# FanTempController.net
KiCad netlist of a schematic drawn in EasyEDA Pro
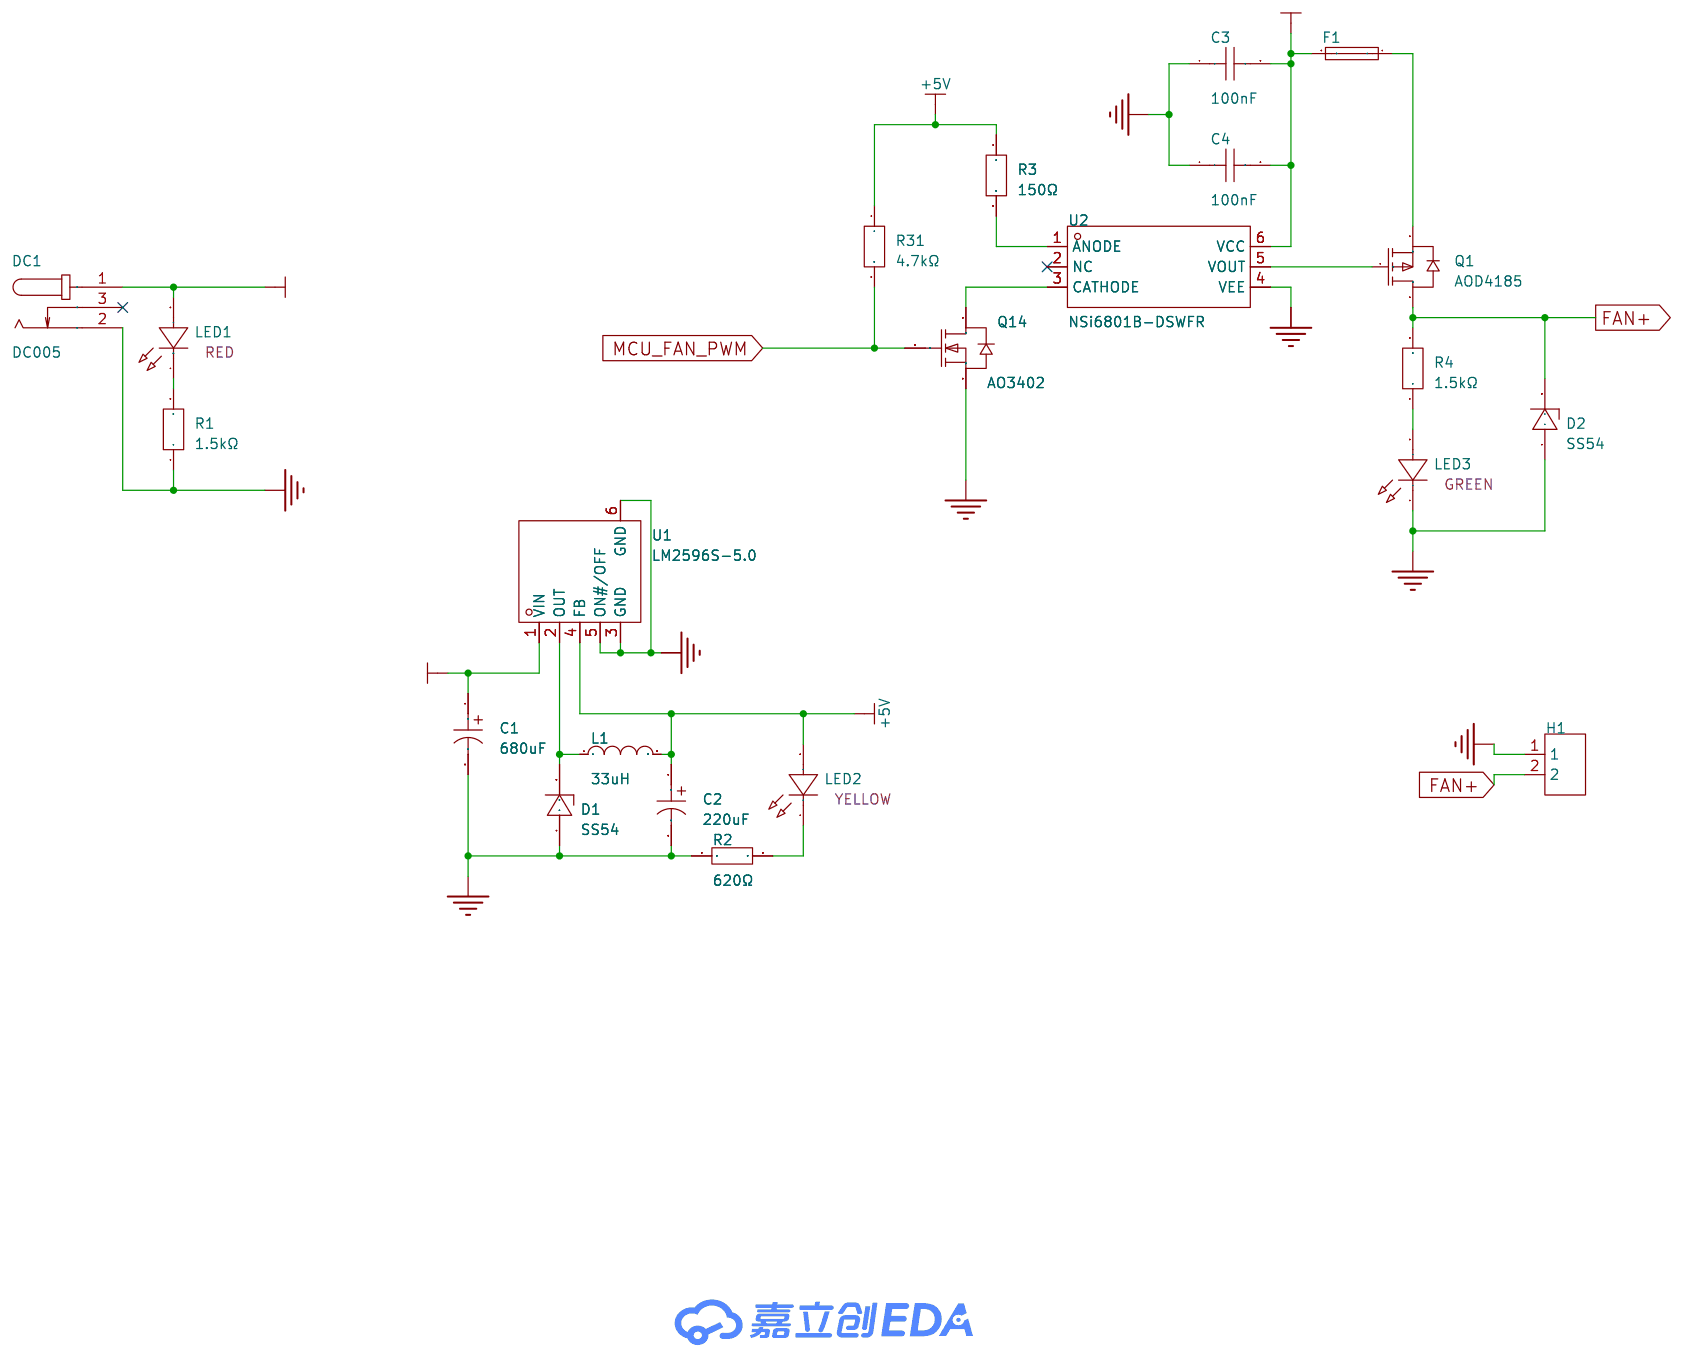
[diagram p0: Power]
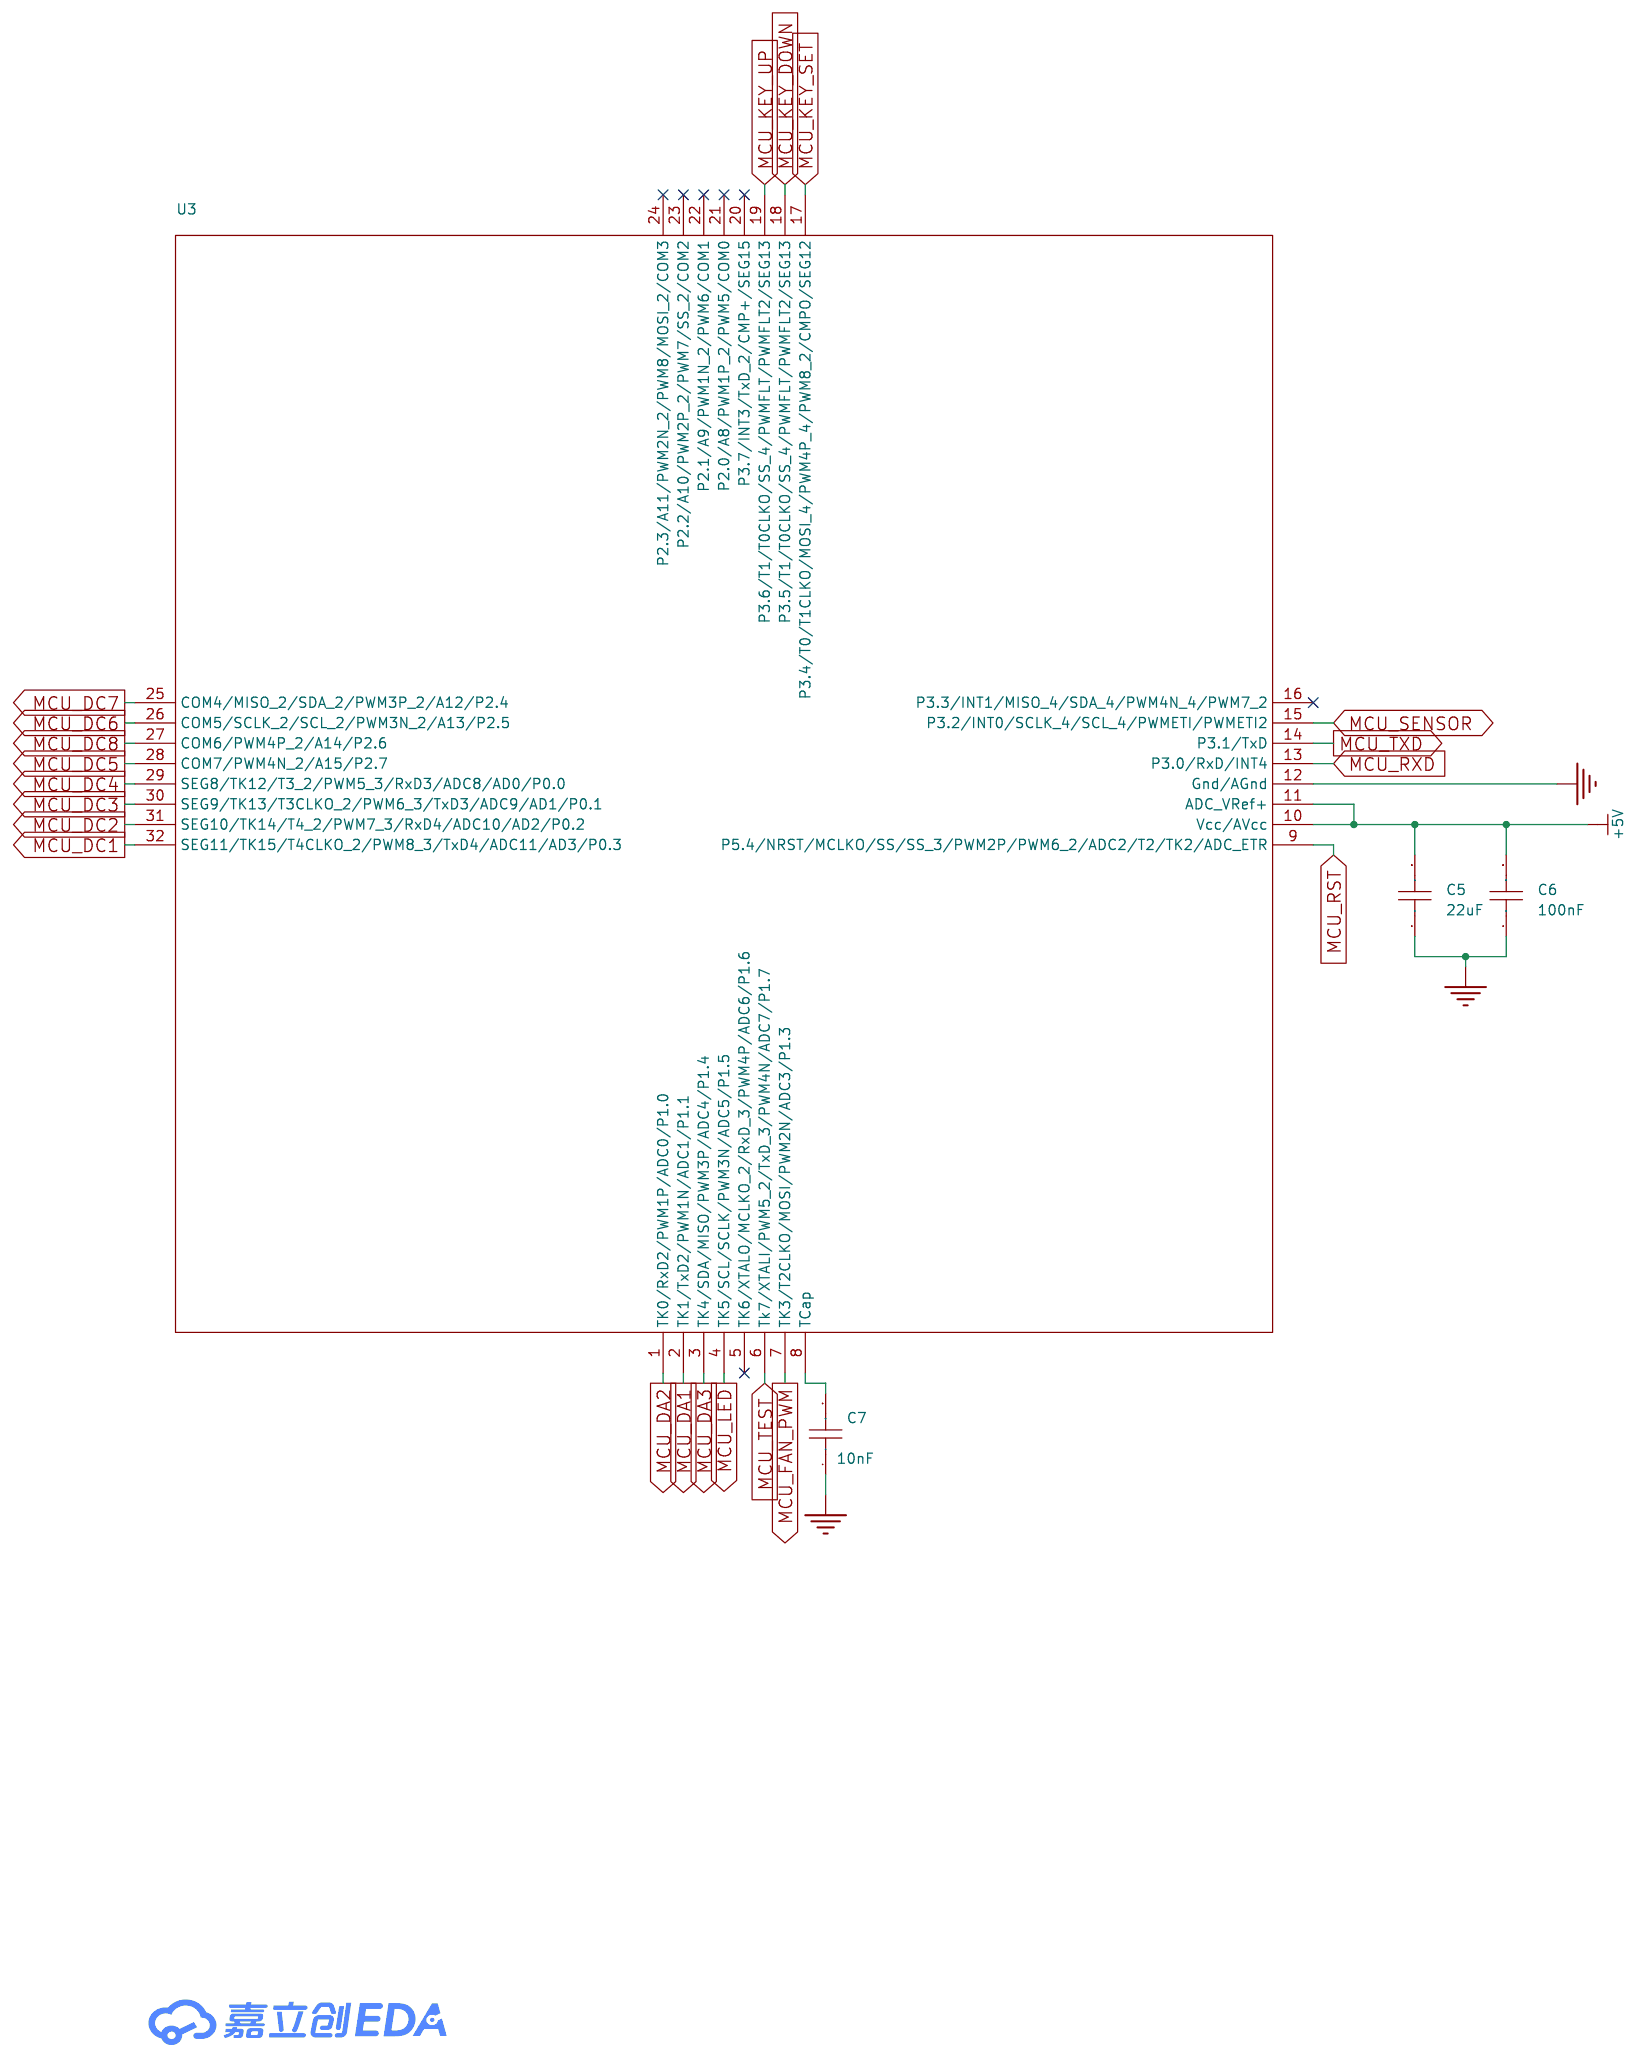
[diagram p1: MCU]
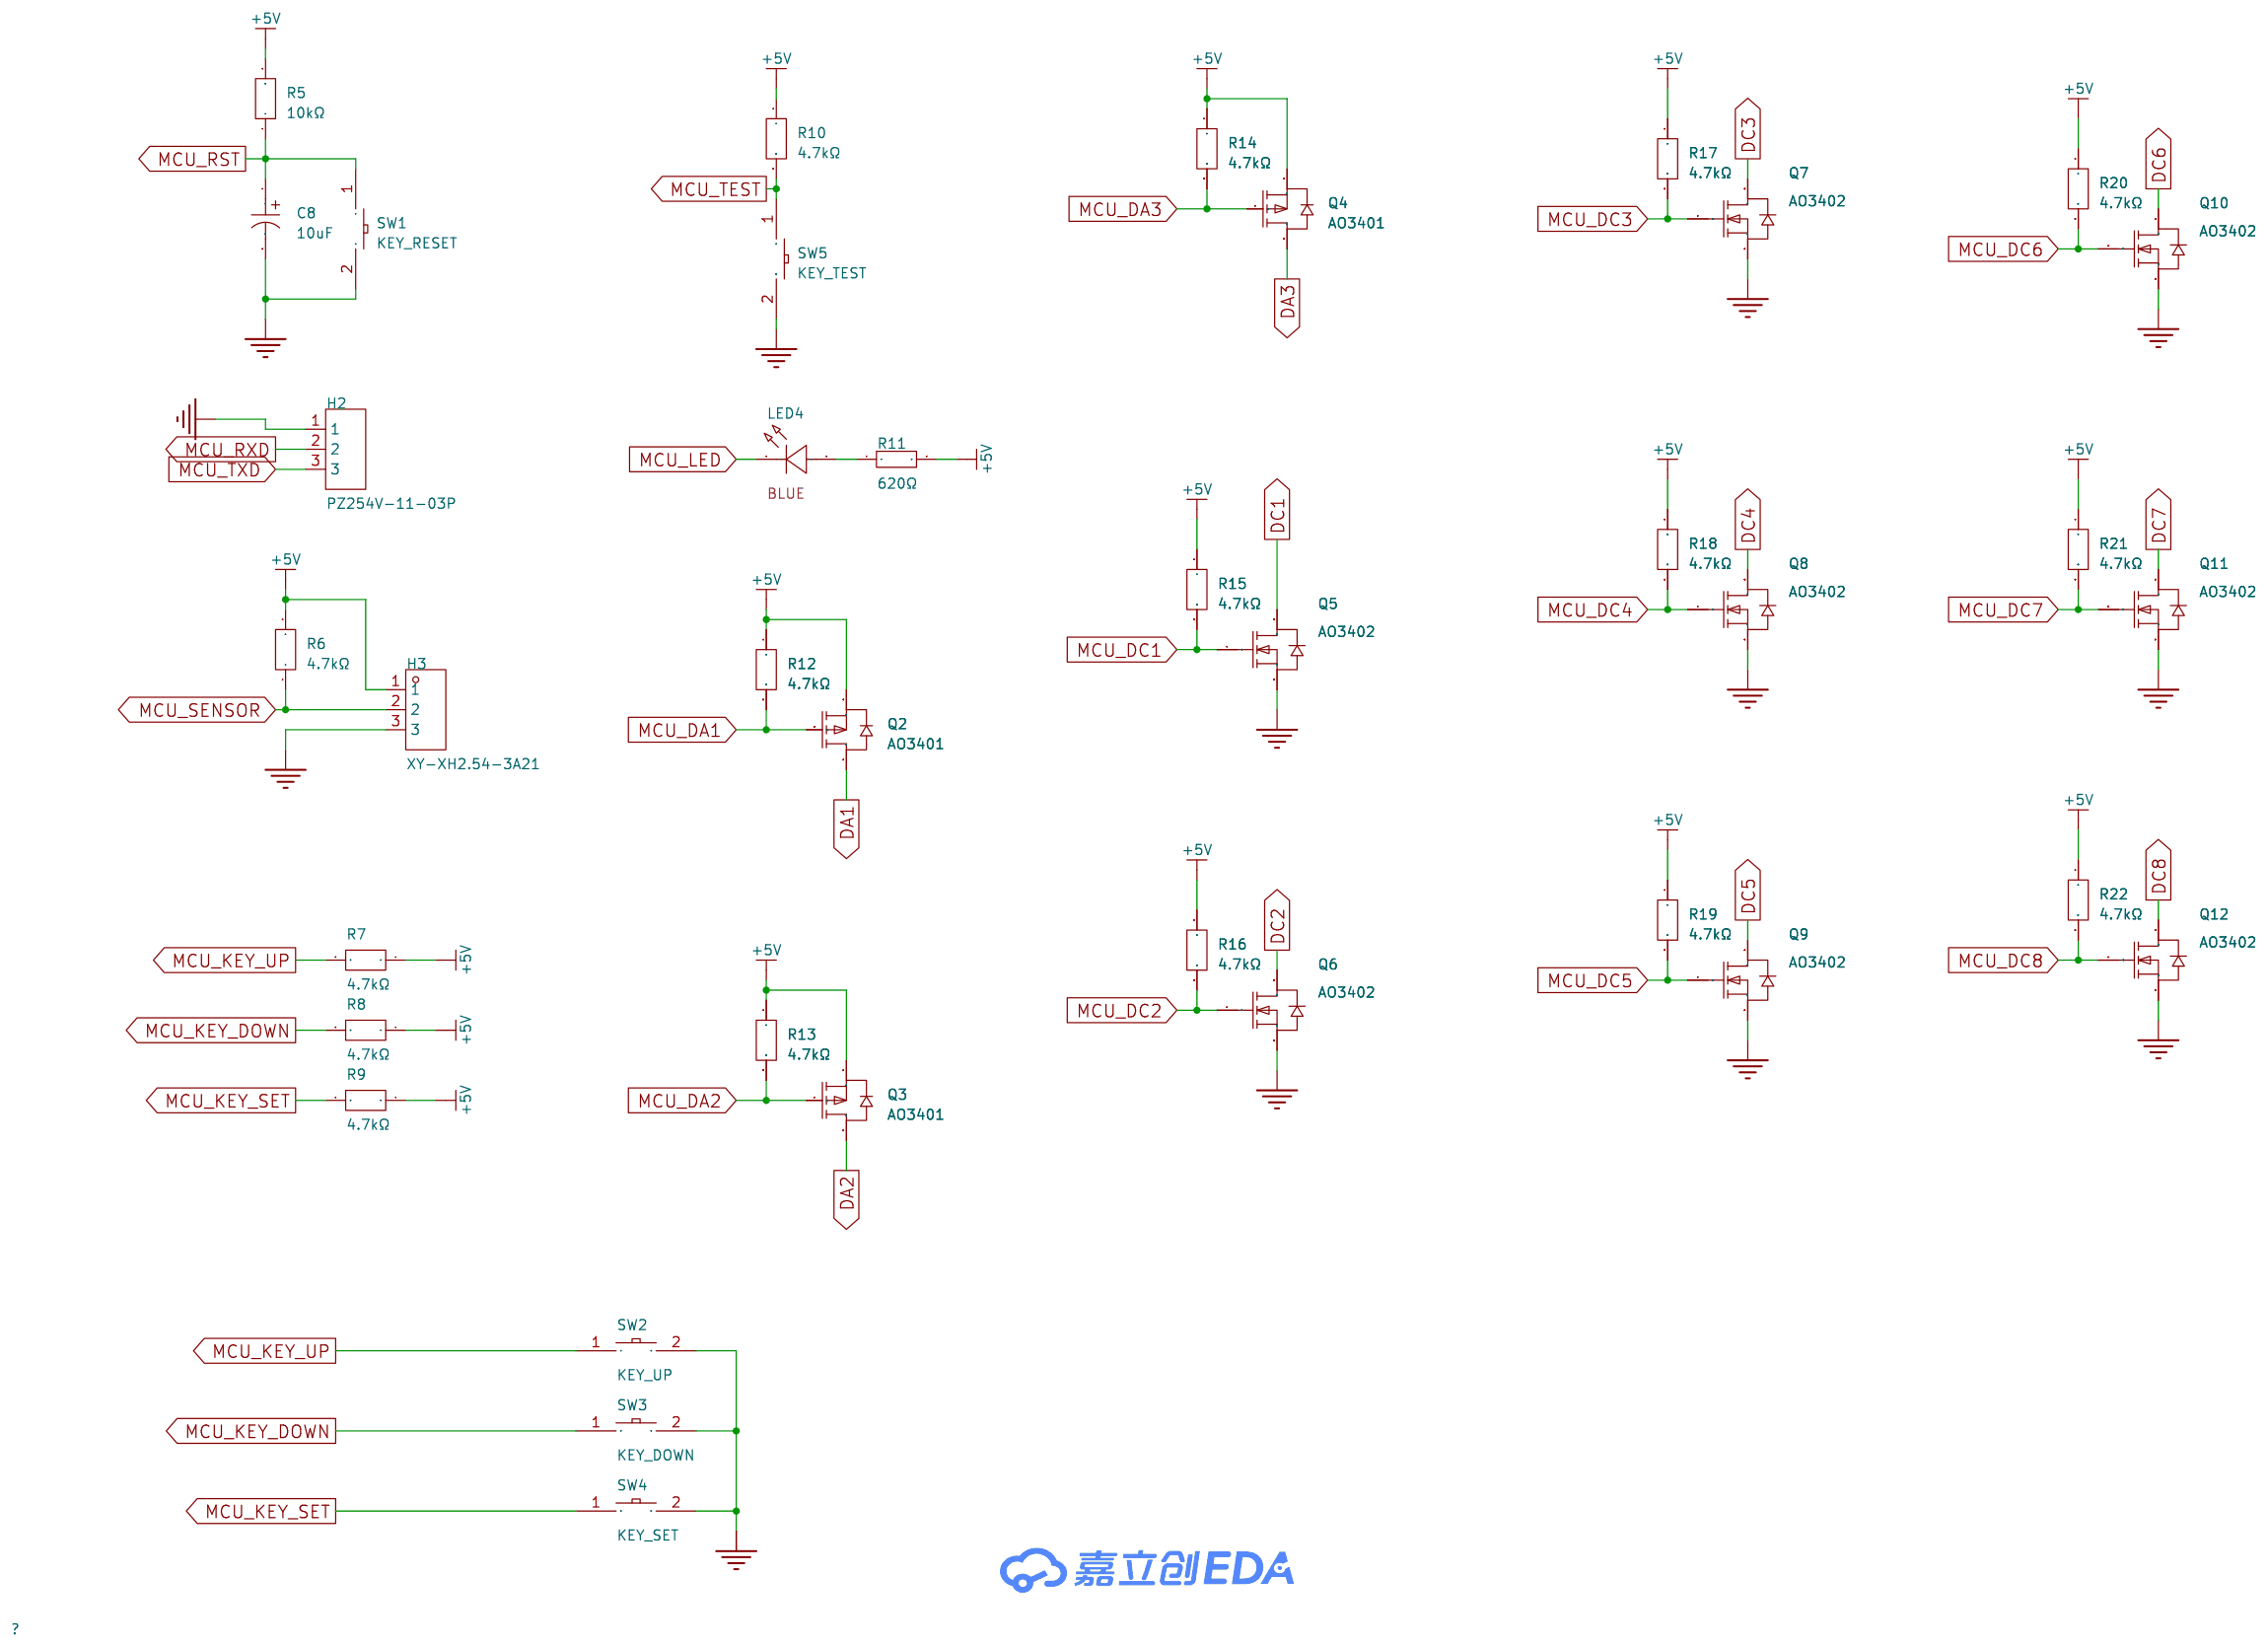
[diagram p2: Others]
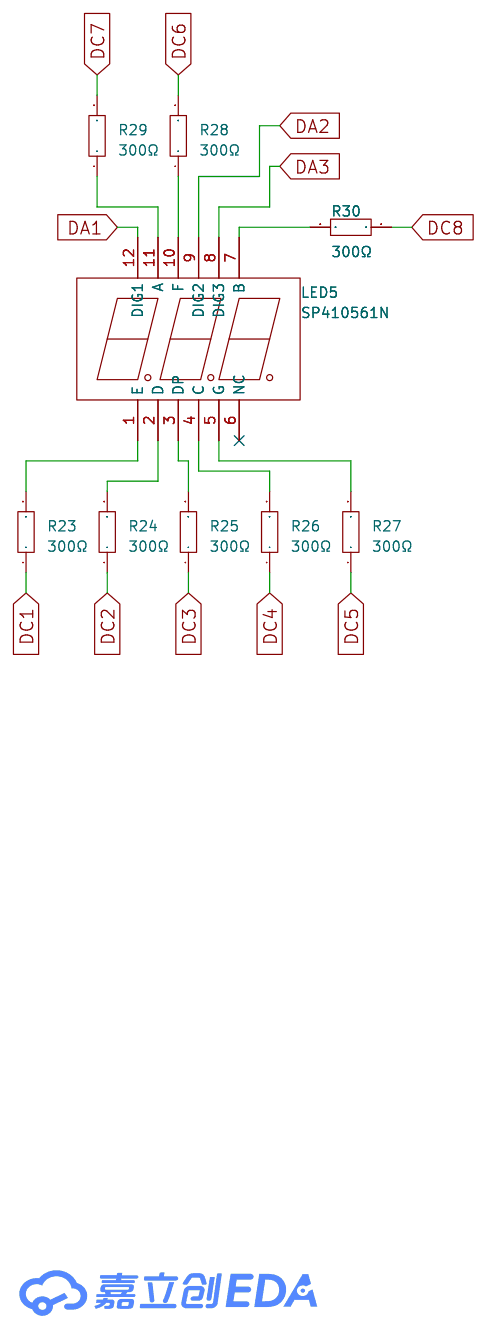
[diagram p3: Display]

(export (version "E")
  (design (tool "Eeschema 10.0.6"))
  (components
    (comp (ref "C1")
      (value "680uF")
      (footprint "easyedapro:CAP-SMD_BD10.0-L10.3-W10.3-LS11.0-FD")
      (description "容值:680uF;精度:±20%;额定电压:25V;纹波电流:670mA@100kHz;")
      (fields
        (field (name "Manufacturer Part") "GVE1E687M1010CN")
        (field (name "Manufacturer") "ACMECON(鼎容)")
      )
      (libsource (lib "easyedapro") (part "GVE1E687M1010CN"))
    )
    (comp (ref "C2")
      (value "220uF")
      (footprint "easyedapro:CAP-SMD_BD8.0-L8.3-W8.3-FD")
      (description "容值:220uF;精度:±20%;额定电压:35V;纹波电流:175mA@120Hz;")
      (fields
        (field (name "Manufacturer Part") "GVT1V227M0810CNVC")
        (field (name "Manufacturer") "HRK(鸿瑞凯电子)")
      )
      (libsource (lib "easyedapro") (part "GVT1V227M0810CNVC"))
    )
    (comp (ref "C3")
      (value "100nF")
      (footprint "easyedapro:C0805")
      (description "容值:100nF;精度:±10%;额定电压:50V;材质(温度系数):X7R;")
      (fields
        (field (name "Manufacturer Part") "C0805X104K5RAC7210")
        (field (name "Manufacturer") "KEMET(基美)")
      )
      (libsource (lib "easyedapro") (part "C0805X104K5RAC7210"))
    )
    (comp (ref "C4")
      (value "100nF")
      (footprint "easyedapro:C0805")
      (description "容值:100nF;精度:±10%;额定电压:50V;材质(温度系数):X7R;")
      (fields
        (field (name "Manufacturer Part") "C0805X104K5RAC7210")
        (field (name "Manufacturer") "KEMET(基美)")
      )
      (libsource (lib "easyedapro") (part "C0805X104K5RAC7210"))
    )
    (comp (ref "D1")
      (value "SS54")
      (footprint "easyedapro:SMA_L4.3-W2.6-LS5.0-FD")
      (description "二极管配置:独立式;正向压降(Vf):550mV@5.0A;直流反向耐压(Vr):40V;整流电流:5A;")
      (fields (field (name "Manufacturer") "宏迦橙"))
      (libsource (lib "easyedapro") (part "SS54_C7420369"))
    )
    (comp (ref "D2")
      (value "SS54")
      (footprint "easyedapro:SMA_L4.3-W2.6-LS5.0-FD")
      (description "二极管配置:独立式;正向压降(Vf):550mV@5.0A;直流反向耐压(Vr):40V;整流电流:5A;")
      (fields (field (name "Manufacturer") "宏迦橙"))
      (libsource (lib "easyedapro") (part "SS54_C7420369"))
    )
    (comp (ref "DC1")
      (value "DC005")
      (footprint "easyedapro:DC-IN-TH_DC005")
      (description "连接器类型:DC电源插座;安装方式:弯插;触点内径:2mm;触点外径:6.3mm;额定电流:500mA;额定电压:30V;工作温度范围:-25°C~+70°C;")
      (fields (field (name "Manufacturer") "SHOU HAN(首韩)"))
      (libsource (lib "easyedapro") (part "DC005_C431533"))
    )
    (comp (ref "F1")
      (value "SMD1812-200-30")
      (footprint "easyedapro:F1812")
      (description "耐压:30V;最大电流:40A;保持电流(Ih):2A;跳闸电流:4A;")
      (fields (field (name "Manufacturer") "宏嘉诚"))
      (libsource (lib "easyedapro") (part "SMD1812-200-30"))
    )
    (comp (ref "H1")
      (value "B25410120-2PB0513-H25A60")
      (footprint "easyedapro:HDR-TH_2P-P2.54-V-M-3")
      (fields (field (name "Manufacturer") "HMTCONN(华明通)"))
      (libsource (lib "easyedapro") (part "B25410120-2PB0513-H25A60"))
    )
    (comp (ref "L1")
      (value "33uH")
      (footprint "easyedapro:IND-SMD_L11.0-W10.2_CXP1050")
      (description "电感值:6.8uH;精度:±20%;额定电流:8.5A;饱和电流(Isat):13A;类型:一体成型电感;")
      (fields
        (field (name "Manufacturer Part") "CXP1050-6R8M-AG(6.8uh)")
        (field (name "Manufacturer") "DMBJ(振宝佳)")
      )
      (libsource (lib "easyedapro") (part "CXP1050-6R8M-AG(6.8UH)"))
    )
    (comp (ref "LED1")
      (value "LTL17KRH5D-012A")
      (footprint "easyedapro:LED-TH_BD3.8-P2.54-RD-RED")
      (description "发光颜色:红色;正向电流:-;")
      (fields (field (name "Manufacturer") "LITEON(光宝)") (field (name "Emitted Color") "RED"))
      (libsource (lib "easyedapro") (part "LTL17KRH5D-012A"))
    )
    (comp (ref "LED2")
      (value "LTL1KHKSD-071A")
      (footprint "easyedapro:LED-TH_BD3.8-P2.54-RD")
      (description "发光颜色:黄色;正向电流:-;")
      (fields (field (name "Manufacturer") "LITEON(光宝)") (field (name "Emitted Color") "YELLOW"))
      (libsource (lib "easyedapro") (part "LTL1KHKSD-071A"))
    )
    (comp (ref "LED3")
      (value "LTL1KHKSD-071A")
      (footprint "easyedapro:LED-TH_BD3.8-P2.54-RD")
      (description "发光颜色:黄色;正向电流:-;")
      (fields (field (name "Manufacturer") "LITEON(光宝)") (field (name "Emitted Color") "GREEN"))
      (libsource (lib "easyedapro") (part "LTL1KHKSD-071A"))
    )
    (comp (ref "Q1")
      (value "AOD4185")
      (footprint "easyedapro:TO-252-3_L6.6-W6.1-P4.57-LS9.9-BR-CW")
      (fields (field (name "Manufacturer") "AOS"))
      (libsource (lib "easyedapro") (part "AOD4185_C400894"))
    )
    (comp (ref "Q14")
      (value "AO3402")
      (footprint "easyedapro:SOT-23_L2.9-W1.3-P1.90-LS2.4-BR")
      (fields (field (name "Manufacturer") "AOS"))
      (libsource (lib "easyedapro") (part "AO3402_C14385"))
    )
    (comp (ref "R1")
      (value "1.5kΩ")
      (footprint "easyedapro:R0805")
      (description "电阻类型:厚膜电阻;阻值:1.5kΩ;精度:±1%;功率:125mW;工作电压:150V;温度系数:±100ppm/°C;")
      (fields (field (name "Manufacturer Part") "FRC0805F1501TS") (field (name "Manufacturer") "FOJAN(富捷)"))
      (libsource (lib "easyedapro") (part "FRC0805F1501TS"))
    )
    (comp (ref "R2")
      (value "620Ω")
      (footprint "easyedapro:R0805")
      (description "电阻类型:厚膜电阻;阻值:620Ω;精度:±1%;功率:125mW;最大工作电压:150V;温度系数:±100ppm/°C;")
      (fields
        (field (name "Manufacturer Part") "0805W8F6200T5E")
        (field (name "Manufacturer") "UNI-ROYAL(厚声)")
      )
      (libsource (lib "easyedapro") (part "0805W8F6200T5E"))
    )
    (comp (ref "R3")
      (value "150Ω")
      (footprint "easyedapro:R0805")
      (description "电阻类型:厚膜电阻;阻值:150Ω;精度:±5%;功率:125mW;最大工作电压:150V;温度系数:±100ppm/°C;")
      (fields (field (name "Manufacturer Part") "FRC0805J151 TS") (field (name "Manufacturer") "FOJAN(富捷)"))
      (libsource (lib "easyedapro") (part "FRC0805J151 TS"))
    )
    (comp (ref "R4")
      (value "1.5kΩ")
      (footprint "easyedapro:R0805")
      (description "电阻类型:厚膜电阻;阻值:1.5kΩ;精度:±1%;功率:125mW;工作电压:150V;温度系数:±100ppm/°C;")
      (fields (field (name "Manufacturer Part") "FRC0805F1501TS") (field (name "Manufacturer") "FOJAN(富捷)"))
      (libsource (lib "easyedapro") (part "FRC0805F1501TS"))
    )
    (comp (ref "R31")
      (value "4.7kΩ")
      (footprint "easyedapro:R0805")
      (description "电阻类型:厚膜电阻;阻值:4.7kΩ;精度:±1%;功率:250mW;工作电压:-;温度系数:±100ppm/°C;")
      (fields (field (name "Manufacturer Part") "SG73P2ATTD4701F") (field (name "Manufacturer") "KOA"))
      (libsource (lib "easyedapro") (part "SG73P2ATTD4701F"))
    )
    (comp (ref "U1")
      (value "LM2596S-5.0")
      (footprint "easyedapro:TO-263-5_L10.1-W8.7-P1.70-LS15.2-BR")
      (description "功能类型:降压型;输出类型:固定;工作电压:-;输出电压:5V;输出电流:-;")
      (fields (field (name "Manufacturer") "TWGMC(台湾迪嘉)"))
      (libsource (lib "easyedapro") (part "LM2596S-5.0_C5276750"))
    )
    (comp (ref "U2")
      (value "NSi6801B-DSWFR")
      (footprint "easyedapro:SOIC-6_L7.5-W4.7-P1.27-LS11.50-TL")
      (fields (field (name "Manufacturer") "NOVOSENSE(纳芯微)"))
      (libsource (lib "easyedapro") (part "NSI6801B-DSWFR"))
    )
    (comp (ref "C5")
      (value "22uF")
      (footprint "easyedapro:C0805")
      (description "容值:22uF;精度:±20%;额定电压:6.3V;温度系数:X7T;")
      (fields
        (field (name "Manufacturer Part") "CL21Z226MQYVPNE")
        (field (name "Manufacturer") "SAMSUNG(三星)")
      )
      (libsource (lib "easyedapro") (part "CL21Z226MQYVPNE"))
    )
    (comp (ref "C6")
      (value "100nF")
      (footprint "easyedapro:C0805")
      (description "容值:100nF;精度:±10%;额定电压:50V;材质(温度系数):X7R;")
      (fields
        (field (name "Manufacturer Part") "C0805X104K5RAC7210")
        (field (name "Manufacturer") "KEMET(基美)")
      )
      (libsource (lib "easyedapro") (part "C0805X104K5RAC7210"))
    )
    (comp (ref "C7")
      (value "10nF")
      (footprint "easyedapro:C0805")
      (description "容值:10nF;精度:±2%;额定电压:50V;材质(温度系数):X8G;")
      (fields
        (field (name "Manufacturer Part") "GCM21B5G1H103GA16L")
        (field (name "Manufacturer") "muRata(村田)")
      )
      (libsource (lib "easyedapro") (part "GCM21B5G1H103GA16L"))
    )
    (comp (ref "U3")
      (value "~")
      (footprint "easyedapro:LQFP-32_L7.0-W7.0-P0.80-LS9.0-BL")
      (description "STC8H4K64TL-40I-LQFP32")
      (libsource (lib "easyedapro") (part "STC8H4K64TL-40I-LQFP32"))
    )
    (comp (ref "C8")
      (value "10uF")
      (footprint "easyedapro:CAP-SMD_BD4.0-L4.3-W4.3-LS5.0-FD")
      (description "容值:10uF;精度:±20%;额定电压:16V;纹波电流:17mA@120Hz;")
      (fields (field (name "Manufacturer Part") "RVT16V10M4X5") (field (name "Manufacturer") "捷而瑞"))
      (libsource (lib "easyedapro") (part "RVT16V10M4X5"))
    )
    (comp (ref "H2")
      (value "PZ254V-11-03P")
      (footprint "easyedapro:HDR-TH_3P-P2.54-V-M")
      (fields (field (name "Manufacturer") "XFCN(兴飞)"))
      (libsource (lib "easyedapro") (part "PZ254V-11-03P_C2937625"))
    )
    (comp (ref "H3")
      (value "XY-XH2.54-3A21")
      (footprint "easyedapro:HDR-TH_3P-P2.50-H-F-W7.0-N")
      (description "插针结构:1x3P;间距:2.54mm;安装方式:弯插;总PIN数:3P;排数:1;每排PIN数:3;行距:2.54mm;额定电流:3A;工作温度范围:-25°C~+85°C;")
      (fields (field (name "Manufacturer") "XYECONN(辛译)"))
      (libsource (lib "easyedapro") (part "XY-XH2.54-3A21"))
    )
    (comp (ref "LED4")
      (value "LTL1KHKSD-071A")
      (footprint "easyedapro:LED-TH_BD3.8-P2.54-RD")
      (description "发光颜色:黄色;正向电流:-;")
      (fields (field (name "Manufacturer") "LITEON(光宝)") (field (name "Emitted Color") "BLUE"))
      (libsource (lib "easyedapro") (part "LTL1KHKSD-071A"))
    )
    (comp (ref "Q2")
      (value "AO3401")
      (footprint "easyedapro:SOT-23-3_L2.9-W1.6-P1.90-LS2.8-BR")
      (description "漏源耐压：-30V 漏极电流：-4.4A 大体积 P MOS")
      (fields (field (name "Manufacturer") "FOSAN(富捷/富信)"))
      (libsource (lib "easyedapro") (part "AO3401_C20634975"))
    )
    (comp (ref "Q3")
      (value "AO3401")
      (footprint "easyedapro:SOT-23-3_L2.9-W1.6-P1.90-LS2.8-BR")
      (description "漏源耐压：-30V 漏极电流：-4.4A 大体积 P MOS")
      (fields (field (name "Manufacturer") "FOSAN(富捷/富信)"))
      (libsource (lib "easyedapro") (part "AO3401_C20634975"))
    )
    (comp (ref "Q4")
      (value "AO3401")
      (footprint "easyedapro:SOT-23-3_L2.9-W1.6-P1.90-LS2.8-BR")
      (description "漏源耐压：-30V 漏极电流：-4.4A 大体积 P MOS")
      (fields (field (name "Manufacturer") "FOSAN(富捷/富信)"))
      (libsource (lib "easyedapro") (part "AO3401_C20634975"))
    )
    (comp (ref "Q5")
      (value "AO3402")
      (footprint "easyedapro:SOT-23_L2.9-W1.3-P1.90-LS2.4-BR")
      (fields (field (name "Manufacturer") "AOS"))
      (libsource (lib "easyedapro") (part "AO3402_C14385"))
    )
    (comp (ref "Q6")
      (value "AO3402")
      (footprint "easyedapro:SOT-23_L2.9-W1.3-P1.90-LS2.4-BR")
      (fields (field (name "Manufacturer") "AOS"))
      (libsource (lib "easyedapro") (part "AO3402_C14385"))
    )
    (comp (ref "Q7")
      (value "AO3402")
      (footprint "easyedapro:SOT-23_L2.9-W1.3-P1.90-LS2.4-BR")
      (fields (field (name "Manufacturer") "AOS"))
      (libsource (lib "easyedapro") (part "AO3402_C14385"))
    )
    (comp (ref "Q8")
      (value "AO3402")
      (footprint "easyedapro:SOT-23_L2.9-W1.3-P1.90-LS2.4-BR")
      (fields (field (name "Manufacturer") "AOS"))
      (libsource (lib "easyedapro") (part "AO3402_C14385"))
    )
    (comp (ref "Q9")
      (value "AO3402")
      (footprint "easyedapro:SOT-23_L2.9-W1.3-P1.90-LS2.4-BR")
      (fields (field (name "Manufacturer") "AOS"))
      (libsource (lib "easyedapro") (part "AO3402_C14385"))
    )
    (comp (ref "Q10")
      (value "AO3402")
      (footprint "easyedapro:SOT-23_L2.9-W1.3-P1.90-LS2.4-BR")
      (fields (field (name "Manufacturer") "AOS"))
      (libsource (lib "easyedapro") (part "AO3402_C14385"))
    )
    (comp (ref "Q11")
      (value "AO3402")
      (footprint "easyedapro:SOT-23_L2.9-W1.3-P1.90-LS2.4-BR")
      (fields (field (name "Manufacturer") "AOS"))
      (libsource (lib "easyedapro") (part "AO3402_C14385"))
    )
    (comp (ref "Q12")
      (value "AO3402")
      (footprint "easyedapro:SOT-23_L2.9-W1.3-P1.90-LS2.4-BR")
      (fields (field (name "Manufacturer") "AOS"))
      (libsource (lib "easyedapro") (part "AO3402_C14385"))
    )
    (comp (ref "R5")
      (value "10kΩ")
      (footprint "easyedapro:R0805")
      (description "阻值:10kΩ;精度:±1%;功率:125mW;")
      (fields (field (name "Manufacturer Part") "RCA0510KFLF") (field (name "Manufacturer") "HKR(香港电阻)"))
      (libsource (lib "easyedapro") (part "RCA0510KFLF"))
    )
    (comp (ref "R6")
      (value "4.7kΩ")
      (footprint "easyedapro:R0805")
      (description "电阻类型:厚膜电阻;阻值:4.7kΩ;精度:±1%;功率:250mW;工作电压:-;温度系数:±100ppm/°C;")
      (fields (field (name "Manufacturer Part") "SG73P2ATTD4701F") (field (name "Manufacturer") "KOA"))
      (libsource (lib "easyedapro") (part "SG73P2ATTD4701F"))
    )
    (comp (ref "R7")
      (value "4.7kΩ")
      (footprint "easyedapro:R0805")
      (description "电阻类型:厚膜电阻;阻值:4.7kΩ;精度:±1%;功率:250mW;工作电压:-;温度系数:±100ppm/°C;")
      (fields (field (name "Manufacturer Part") "SG73P2ATTD4701F") (field (name "Manufacturer") "KOA"))
      (libsource (lib "easyedapro") (part "SG73P2ATTD4701F"))
    )
    (comp (ref "R8")
      (value "4.7kΩ")
      (footprint "easyedapro:R0805")
      (description "电阻类型:厚膜电阻;阻值:4.7kΩ;精度:±1%;功率:250mW;工作电压:-;温度系数:±100ppm/°C;")
      (fields (field (name "Manufacturer Part") "SG73P2ATTD4701F") (field (name "Manufacturer") "KOA"))
      (libsource (lib "easyedapro") (part "SG73P2ATTD4701F"))
    )
    (comp (ref "R9")
      (value "4.7kΩ")
      (footprint "easyedapro:R0805")
      (description "电阻类型:厚膜电阻;阻值:4.7kΩ;精度:±1%;功率:250mW;工作电压:-;温度系数:±100ppm/°C;")
      (fields (field (name "Manufacturer Part") "SG73P2ATTD4701F") (field (name "Manufacturer") "KOA"))
      (libsource (lib "easyedapro") (part "SG73P2ATTD4701F"))
    )
    (comp (ref "R10")
      (value "4.7kΩ")
      (footprint "easyedapro:R0805")
      (description "电阻类型:厚膜电阻;阻值:4.7kΩ;精度:±1%;功率:250mW;工作电压:-;温度系数:±100ppm/°C;")
      (fields (field (name "Manufacturer Part") "SG73P2ATTD4701F") (field (name "Manufacturer") "KOA"))
      (libsource (lib "easyedapro") (part "SG73P2ATTD4701F"))
    )
    (comp (ref "R11")
      (value "620Ω")
      (footprint "easyedapro:R0805")
      (description "电阻类型:厚膜电阻;阻值:620Ω;精度:±1%;功率:125mW;最大工作电压:150V;温度系数:±100ppm/°C;")
      (fields
        (field (name "Manufacturer Part") "0805W8F6200T5E")
        (field (name "Manufacturer") "UNI-ROYAL(厚声)")
      )
      (libsource (lib "easyedapro") (part "0805W8F6200T5E"))
    )
    (comp (ref "R12")
      (value "4.7kΩ")
      (footprint "easyedapro:R0805")
      (description "电阻类型:厚膜电阻;阻值:4.7kΩ;精度:±1%;功率:250mW;工作电压:-;温度系数:±100ppm/°C;")
      (fields (field (name "Manufacturer Part") "SG73P2ATTD4701F") (field (name "Manufacturer") "KOA"))
      (libsource (lib "easyedapro") (part "SG73P2ATTD4701F"))
    )
    (comp (ref "R13")
      (value "4.7kΩ")
      (footprint "easyedapro:R0805")
      (description "电阻类型:厚膜电阻;阻值:4.7kΩ;精度:±1%;功率:250mW;工作电压:-;温度系数:±100ppm/°C;")
      (fields (field (name "Manufacturer Part") "SG73P2ATTD4701F") (field (name "Manufacturer") "KOA"))
      (libsource (lib "easyedapro") (part "SG73P2ATTD4701F"))
    )
    (comp (ref "R14")
      (value "4.7kΩ")
      (footprint "easyedapro:R0805")
      (description "电阻类型:厚膜电阻;阻值:4.7kΩ;精度:±1%;功率:250mW;工作电压:-;温度系数:±100ppm/°C;")
      (fields (field (name "Manufacturer Part") "SG73P2ATTD4701F") (field (name "Manufacturer") "KOA"))
      (libsource (lib "easyedapro") (part "SG73P2ATTD4701F"))
    )
    (comp (ref "R15")
      (value "4.7kΩ")
      (footprint "easyedapro:R0805")
      (description "电阻类型:厚膜电阻;阻值:4.7kΩ;精度:±1%;功率:250mW;工作电压:-;温度系数:±100ppm/°C;")
      (fields (field (name "Manufacturer Part") "SG73P2ATTD4701F") (field (name "Manufacturer") "KOA"))
      (libsource (lib "easyedapro") (part "SG73P2ATTD4701F"))
    )
    (comp (ref "R16")
      (value "4.7kΩ")
      (footprint "easyedapro:R0805")
      (description "电阻类型:厚膜电阻;阻值:4.7kΩ;精度:±1%;功率:250mW;工作电压:-;温度系数:±100ppm/°C;")
      (fields (field (name "Manufacturer Part") "SG73P2ATTD4701F") (field (name "Manufacturer") "KOA"))
      (libsource (lib "easyedapro") (part "SG73P2ATTD4701F"))
    )
    (comp (ref "R17")
      (value "4.7kΩ")
      (footprint "easyedapro:R0805")
      (description "电阻类型:厚膜电阻;阻值:4.7kΩ;精度:±1%;功率:250mW;工作电压:-;温度系数:±100ppm/°C;")
      (fields (field (name "Manufacturer Part") "SG73P2ATTD4701F") (field (name "Manufacturer") "KOA"))
      (libsource (lib "easyedapro") (part "SG73P2ATTD4701F"))
    )
    (comp (ref "R18")
      (value "4.7kΩ")
      (footprint "easyedapro:R0805")
      (description "电阻类型:厚膜电阻;阻值:4.7kΩ;精度:±1%;功率:250mW;工作电压:-;温度系数:±100ppm/°C;")
      (fields (field (name "Manufacturer Part") "SG73P2ATTD4701F") (field (name "Manufacturer") "KOA"))
      (libsource (lib "easyedapro") (part "SG73P2ATTD4701F"))
    )
    (comp (ref "R19")
      (value "4.7kΩ")
      (footprint "easyedapro:R0805")
      (description "电阻类型:厚膜电阻;阻值:4.7kΩ;精度:±1%;功率:250mW;工作电压:-;温度系数:±100ppm/°C;")
      (fields (field (name "Manufacturer Part") "SG73P2ATTD4701F") (field (name "Manufacturer") "KOA"))
      (libsource (lib "easyedapro") (part "SG73P2ATTD4701F"))
    )
    (comp (ref "R20")
      (value "4.7kΩ")
      (footprint "easyedapro:R0805")
      (description "电阻类型:厚膜电阻;阻值:4.7kΩ;精度:±1%;功率:250mW;工作电压:-;温度系数:±100ppm/°C;")
      (fields (field (name "Manufacturer Part") "SG73P2ATTD4701F") (field (name "Manufacturer") "KOA"))
      (libsource (lib "easyedapro") (part "SG73P2ATTD4701F"))
    )
    (comp (ref "R21")
      (value "4.7kΩ")
      (footprint "easyedapro:R0805")
      (description "电阻类型:厚膜电阻;阻值:4.7kΩ;精度:±1%;功率:250mW;工作电压:-;温度系数:±100ppm/°C;")
      (fields (field (name "Manufacturer Part") "SG73P2ATTD4701F") (field (name "Manufacturer") "KOA"))
      (libsource (lib "easyedapro") (part "SG73P2ATTD4701F"))
    )
    (comp (ref "R22")
      (value "4.7kΩ")
      (footprint "easyedapro:R0805")
      (description "电阻类型:厚膜电阻;阻值:4.7kΩ;精度:±1%;功率:250mW;工作电压:-;温度系数:±100ppm/°C;")
      (fields (field (name "Manufacturer Part") "SG73P2ATTD4701F") (field (name "Manufacturer") "KOA"))
      (libsource (lib "easyedapro") (part "SG73P2ATTD4701F"))
    )
    (comp (ref "SW1")
      (value "KEY_RESET")
      (footprint "easyedapro:SW-SMD_L6.0-W3.5-LS8.1_UK-B0306T-WB-250JZ")
      (description "作用力:2.5N;开关长度:6mm;开关宽度:3.5mm;开关高度:2.5mm;")
      (fields
        (field (name "Manufacturer Part") "UK-B0306T-WB-250JZ")
        (field (name "Manufacturer") "USAKRO(美韩)")
      )
      (libsource (lib "easyedapro") (part "UK-B0306T-WB-250JZ"))
    )
    (comp (ref "SW2")
      (value "KEY_UP")
      (footprint "easyedapro:SW-SMD_L6.0-W3.5-LS8.1_UK-B0306T-WB-250JZ")
      (description "作用力:2.5N;开关长度:6mm;开关宽度:3.5mm;开关高度:2.5mm;")
      (fields
        (field (name "Manufacturer Part") "UK-B0306T-WB-250JZ")
        (field (name "Manufacturer") "USAKRO(美韩)")
      )
      (libsource (lib "easyedapro") (part "UK-B0306T-WB-250JZ"))
    )
    (comp (ref "SW3")
      (value "KEY_DOWN")
      (footprint "easyedapro:SW-SMD_L6.0-W3.5-LS8.1_UK-B0306T-WB-250JZ")
      (description "作用力:2.5N;开关长度:6mm;开关宽度:3.5mm;开关高度:2.5mm;")
      (fields
        (field (name "Manufacturer Part") "UK-B0306T-WB-250JZ")
        (field (name "Manufacturer") "USAKRO(美韩)")
      )
      (libsource (lib "easyedapro") (part "UK-B0306T-WB-250JZ"))
    )
    (comp (ref "SW4")
      (value "KEY_SET")
      (footprint "easyedapro:SW-SMD_L6.0-W3.5-LS8.1_UK-B0306T-WB-250JZ")
      (description "作用力:2.5N;开关长度:6mm;开关宽度:3.5mm;开关高度:2.5mm;")
      (fields
        (field (name "Manufacturer Part") "UK-B0306T-WB-250JZ")
        (field (name "Manufacturer") "USAKRO(美韩)")
      )
      (libsource (lib "easyedapro") (part "UK-B0306T-WB-250JZ"))
    )
    (comp (ref "SW5")
      (value "KEY_TEST")
      (footprint "easyedapro:SW-SMD_L6.0-W3.5-LS8.1_UK-B0306T-WB-250JZ")
      (description "作用力:2.5N;开关长度:6mm;开关宽度:3.5mm;开关高度:2.5mm;")
      (fields
        (field (name "Manufacturer Part") "UK-B0306T-WB-250JZ")
        (field (name "Manufacturer") "USAKRO(美韩)")
      )
      (libsource (lib "easyedapro") (part "UK-B0306T-WB-250JZ"))
    )
    (comp (ref "LED5")
      (value "SP410561N")
      (footprint "easyedapro:LED-SEG-TH_12P-L37.6-W19.0-P2.54-S15.24-BL")
      (description "数码管位数:3位;发光颜色:红色;LED极性:共阳极;数字/字母大小(英寸):0.56;")
      (fields (field (name "Manufacturer") "ARKLED(方舟)"))
      (libsource (lib "easyedapro") (part "SP410561N"))
    )
    (comp (ref "R23")
      (value "300Ω")
      (footprint "easyedapro:R0805")
      (description "电阻类型:厚膜电阻;阻值:300Ω;精度:±1%;功率:125mW;最大工作电压:150V;温度系数:±100ppm/°C;")
      (fields
        (field (name "Manufacturer Part") "0805W8F3000T5E")
        (field (name "Manufacturer") "UNI-ROYAL(厚声)")
      )
      (libsource (lib "easyedapro") (part "0805W8F3000T5E"))
    )
    (comp (ref "R24")
      (value "300Ω")
      (footprint "easyedapro:R0805")
      (description "电阻类型:厚膜电阻;阻值:300Ω;精度:±1%;功率:125mW;最大工作电压:150V;温度系数:±100ppm/°C;")
      (fields
        (field (name "Manufacturer Part") "0805W8F3000T5E")
        (field (name "Manufacturer") "UNI-ROYAL(厚声)")
      )
      (libsource (lib "easyedapro") (part "0805W8F3000T5E"))
    )
    (comp (ref "R25")
      (value "300Ω")
      (footprint "easyedapro:R0805")
      (description "电阻类型:厚膜电阻;阻值:300Ω;精度:±1%;功率:125mW;最大工作电压:150V;温度系数:±100ppm/°C;")
      (fields
        (field (name "Manufacturer Part") "0805W8F3000T5E")
        (field (name "Manufacturer") "UNI-ROYAL(厚声)")
      )
      (libsource (lib "easyedapro") (part "0805W8F3000T5E"))
    )
    (comp (ref "R26")
      (value "300Ω")
      (footprint "easyedapro:R0805")
      (description "电阻类型:厚膜电阻;阻值:300Ω;精度:±1%;功率:125mW;最大工作电压:150V;温度系数:±100ppm/°C;")
      (fields
        (field (name "Manufacturer Part") "0805W8F3000T5E")
        (field (name "Manufacturer") "UNI-ROYAL(厚声)")
      )
      (libsource (lib "easyedapro") (part "0805W8F3000T5E"))
    )
    (comp (ref "R27")
      (value "300Ω")
      (footprint "easyedapro:R0805")
      (description "电阻类型:厚膜电阻;阻值:300Ω;精度:±1%;功率:125mW;最大工作电压:150V;温度系数:±100ppm/°C;")
      (fields
        (field (name "Manufacturer Part") "0805W8F3000T5E")
        (field (name "Manufacturer") "UNI-ROYAL(厚声)")
      )
      (libsource (lib "easyedapro") (part "0805W8F3000T5E"))
    )
    (comp (ref "R28")
      (value "300Ω")
      (footprint "easyedapro:R0805")
      (description "电阻类型:厚膜电阻;阻值:300Ω;精度:±1%;功率:125mW;最大工作电压:150V;温度系数:±100ppm/°C;")
      (fields
        (field (name "Manufacturer Part") "0805W8F3000T5E")
        (field (name "Manufacturer") "UNI-ROYAL(厚声)")
      )
      (libsource (lib "easyedapro") (part "0805W8F3000T5E"))
    )
    (comp (ref "R29")
      (value "300Ω")
      (footprint "easyedapro:R0805")
      (description "电阻类型:厚膜电阻;阻值:300Ω;精度:±1%;功率:125mW;最大工作电压:150V;温度系数:±100ppm/°C;")
      (fields
        (field (name "Manufacturer Part") "0805W8F3000T5E")
        (field (name "Manufacturer") "UNI-ROYAL(厚声)")
      )
      (libsource (lib "easyedapro") (part "0805W8F3000T5E"))
    )
    (comp (ref "R30")
      (value "300Ω")
      (footprint "easyedapro:R0805")
      (description "电阻类型:厚膜电阻;阻值:300Ω;精度:±1%;功率:125mW;最大工作电压:150V;温度系数:±100ppm/°C;")
      (fields
        (field (name "Manufacturer Part") "0805W8F3000T5E")
        (field (name "Manufacturer") "UNI-ROYAL(厚声)")
      )
      (libsource (lib "easyedapro") (part "0805W8F3000T5E"))
    )
  )
  (nets
    (net (code "1") (name "+5V") (class "Default")
      (node (ref "C2") (pin "1") (pinfunction "1_1") (pintype "input"))
      (node (ref "C5") (pin "2") (pinfunction "2_2") (pintype "unspecified"))
      (node (ref "C6") (pin "2") (pinfunction "2_2") (pintype "unspecified"))
      (node (ref "H3") (pin "1") (pinfunction "1_1") (pintype "unspecified"))
      (node (ref "L1") (pin "2") (pinfunction "2_2") (pintype "unspecified"))
      (node (ref "LED2") (pin "2") (pinfunction "A_2") (pintype "unspecified"))
      (node (ref "Q2") (pin "2") (pinfunction "S_2") (pintype "unspecified"))
      (node (ref "Q3") (pin "2") (pinfunction "S_2") (pintype "unspecified"))
      (node (ref "Q4") (pin "2") (pinfunction "S_2") (pintype "unspecified"))
      (node (ref "R10") (pin "1") (pinfunction "1_1") (pintype "unspecified"))
      (node (ref "R11") (pin "2") (pinfunction "2_2") (pintype "input"))
      (node (ref "R12") (pin "1") (pinfunction "1_1") (pintype "unspecified"))
      (node (ref "R13") (pin "1") (pinfunction "1_1") (pintype "unspecified"))
      (node (ref "R14") (pin "1") (pinfunction "1_1") (pintype "unspecified"))
      (node (ref "R15") (pin "1") (pinfunction "1_1") (pintype "unspecified"))
      (node (ref "R16") (pin "1") (pinfunction "1_1") (pintype "unspecified"))
      (node (ref "R17") (pin "1") (pinfunction "1_1") (pintype "unspecified"))
      (node (ref "R18") (pin "1") (pinfunction "1_1") (pintype "unspecified"))
      (node (ref "R19") (pin "1") (pinfunction "1_1") (pintype "unspecified"))
      (node (ref "R20") (pin "1") (pinfunction "1_1") (pintype "unspecified"))
      (node (ref "R21") (pin "1") (pinfunction "1_1") (pintype "unspecified"))
      (node (ref "R22") (pin "1") (pinfunction "1_1") (pintype "unspecified"))
      (node (ref "R3") (pin "1") (pinfunction "1_1") (pintype "unspecified"))
      (node (ref "R31") (pin "1") (pinfunction "1_1") (pintype "unspecified"))
      (node (ref "R5") (pin "2") (pinfunction "2_2") (pintype "unspecified"))
      (node (ref "R6") (pin "2") (pinfunction "2_2") (pintype "unspecified"))
      (node (ref "R7") (pin "1") (pinfunction "1_1") (pintype "unspecified"))
      (node (ref "R8") (pin "1") (pinfunction "1_1") (pintype "unspecified"))
      (node (ref "R9") (pin "1") (pinfunction "1_1") (pintype "unspecified"))
      (node (ref "U1") (pin "4") (pinfunction "FB_4") (pintype "unspecified"))
      (node (ref "U3") (pin "10") (pinfunction "Vcc/AVcc_10") (pintype "input"))
      (node (ref "U3") (pin "11") (pinfunction "ADC_VRef+_11") (pintype "input"))
    )
    (net (code "2") (name "DA1") (class "Default")
      (node (ref "LED5") (pin "12") (pinfunction "DIG1_12") (pintype "unspecified"))
      (node (ref "Q2") (pin "3") (pinfunction "D_3") (pintype "unspecified"))
    )
    (net (code "3") (name "DA2") (class "Default")
      (node (ref "LED5") (pin "9") (pinfunction "DIG2_9") (pintype "unspecified"))
      (node (ref "Q3") (pin "3") (pinfunction "D_3") (pintype "unspecified"))
    )
    (net (code "4") (name "DA3") (class "Default")
      (node (ref "LED5") (pin "8") (pinfunction "DIG3_8") (pintype "unspecified"))
      (node (ref "Q4") (pin "3") (pinfunction "D_3") (pintype "unspecified"))
    )
    (net (code "5") (name "DC1") (class "Default")
      (node (ref "Q5") (pin "3") (pinfunction "D_3") (pintype "unspecified"))
      (node (ref "R23") (pin "1") (pinfunction "1_1") (pintype "input"))
    )
    (net (code "6") (name "DC2") (class "Default")
      (node (ref "Q6") (pin "3") (pinfunction "D_3") (pintype "unspecified"))
      (node (ref "R24") (pin "1") (pinfunction "1_1") (pintype "input"))
    )
    (net (code "7") (name "DC3") (class "Default")
      (node (ref "Q7") (pin "3") (pinfunction "D_3") (pintype "unspecified"))
      (node (ref "R25") (pin "1") (pinfunction "1_1") (pintype "input"))
    )
    (net (code "8") (name "DC4") (class "Default")
      (node (ref "Q8") (pin "3") (pinfunction "D_3") (pintype "unspecified"))
      (node (ref "R26") (pin "1") (pinfunction "1_1") (pintype "input"))
    )
    (net (code "9") (name "DC5") (class "Default")
      (node (ref "Q9") (pin "3") (pinfunction "D_3") (pintype "unspecified"))
      (node (ref "R27") (pin "1") (pinfunction "1_1") (pintype "input"))
    )
    (net (code "10") (name "DC6") (class "Default")
      (node (ref "Q10") (pin "3") (pinfunction "D_3") (pintype "unspecified"))
      (node (ref "R28") (pin "2") (pinfunction "2_2") (pintype "input"))
    )
    (net (code "11") (name "DC7") (class "Default")
      (node (ref "Q11") (pin "3") (pinfunction "D_3") (pintype "unspecified"))
      (node (ref "R29") (pin "2") (pinfunction "2_2") (pintype "input"))
    )
    (net (code "12") (name "DC8") (class "Default")
      (node (ref "Q12") (pin "3") (pinfunction "D_3") (pintype "unspecified"))
      (node (ref "R30") (pin "1") (pinfunction "1_1") (pintype "input"))
    )
    (net (code "13") (name "FAN+") (class "Default")
      (node (ref "D2") (pin "2") (pinfunction "K_2") (pintype "unspecified"))
      (node (ref "H1") (pin "2") (pinfunction "2_2") (pintype "unspecified"))
      (node (ref "Q1") (pin "2") (pinfunction "D_2") (pintype "unspecified"))
      (node (ref "R4") (pin "2") (pinfunction "2_2") (pintype "unspecified"))
    )
    (net (code "14") (name "GND") (class "Default")
      (node (ref "C1") (pin "2") (pinfunction "2_2") (pintype "input"))
      (node (ref "C2") (pin "2") (pinfunction "2_2") (pintype "input"))
      (node (ref "C3") (pin "1") (pinfunction "1_1") (pintype "unspecified"))
      (node (ref "C4") (pin "1") (pinfunction "1_1") (pintype "unspecified"))
      (node (ref "C5") (pin "1") (pinfunction "1_1") (pintype "unspecified"))
      (node (ref "C6") (pin "1") (pinfunction "1_1") (pintype "unspecified"))
      (node (ref "C7") (pin "1") (pinfunction "1_1") (pintype "unspecified"))
      (node (ref "C8") (pin "2") (pinfunction "2_2") (pintype "input"))
      (node (ref "D1") (pin "1") (pinfunction "A_1") (pintype "unspecified"))
      (node (ref "D2") (pin "1") (pinfunction "A_1") (pintype "unspecified"))
      (node (ref "DC1") (pin "2") (pinfunction "2_2") (pintype "unspecified"))
      (node (ref "H1") (pin "1") (pinfunction "1_1") (pintype "unspecified"))
      (node (ref "H2") (pin "1") (pinfunction "1_1") (pintype "unspecified"))
      (node (ref "H3") (pin "3") (pinfunction "3_3") (pintype "unspecified"))
      (node (ref "LED3") (pin "1") (pinfunction "K_1") (pintype "unspecified"))
      (node (ref "Q10") (pin "2") (pinfunction "S_2") (pintype "unspecified"))
      (node (ref "Q11") (pin "2") (pinfunction "S_2") (pintype "unspecified"))
      (node (ref "Q12") (pin "2") (pinfunction "S_2") (pintype "unspecified"))
      (node (ref "Q14") (pin "2") (pinfunction "S_2") (pintype "unspecified"))
      (node (ref "Q5") (pin "2") (pinfunction "S_2") (pintype "unspecified"))
      (node (ref "Q6") (pin "2") (pinfunction "S_2") (pintype "unspecified"))
      (node (ref "Q7") (pin "2") (pinfunction "S_2") (pintype "unspecified"))
      (node (ref "Q8") (pin "2") (pinfunction "S_2") (pintype "unspecified"))
      (node (ref "Q9") (pin "2") (pinfunction "S_2") (pintype "unspecified"))
      (node (ref "R1") (pin "1") (pinfunction "1_1") (pintype "unspecified"))
      (node (ref "R2") (pin "1") (pinfunction "1_1") (pintype "input"))
      (node (ref "SW1") (pin "2") (pinfunction "2_2") (pintype "unspecified"))
      (node (ref "SW2") (pin "2") (pinfunction "2_2") (pintype "unspecified"))
      (node (ref "SW3") (pin "2") (pinfunction "2_2") (pintype "unspecified"))
      (node (ref "SW4") (pin "2") (pinfunction "2_2") (pintype "unspecified"))
      (node (ref "SW5") (pin "2") (pinfunction "2_2") (pintype "unspecified"))
      (node (ref "U1") (pin "3") (pinfunction "GND_3") (pintype "unspecified"))
      (node (ref "U1") (pin "5") (pinfunction "ON#/OFF_5") (pintype "unspecified"))
      (node (ref "U1") (pin "6") (pinfunction "GND_6") (pintype "unspecified"))
      (node (ref "U2") (pin "4") (pinfunction "VEE_4") (pintype "unspecified"))
      (node (ref "U3") (pin "12") (pinfunction "Gnd/AGnd_12") (pintype "input"))
    )
    (net (code "15") (name "MCU_DA1") (class "Default")
      (node (ref "Q2") (pin "1") (pinfunction "G_1") (pintype "unspecified"))
      (node (ref "R12") (pin "2") (pinfunction "2_2") (pintype "unspecified"))
      (node (ref "U3") (pin "2") (pinfunction "TK1/TxD2/PWM1N/ADC1/P1.1_2") (pintype "input"))
    )
    (net (code "16") (name "MCU_DA2") (class "Default")
      (node (ref "Q3") (pin "1") (pinfunction "G_1") (pintype "unspecified"))
      (node (ref "R13") (pin "2") (pinfunction "2_2") (pintype "unspecified"))
      (node (ref "U3") (pin "1") (pinfunction "TK0/RxD2/PWM1P/ADC0/P1.0_1") (pintype "input"))
    )
    (net (code "17") (name "MCU_DA3") (class "Default")
      (node (ref "Q4") (pin "1") (pinfunction "G_1") (pintype "unspecified"))
      (node (ref "R14") (pin "2") (pinfunction "2_2") (pintype "unspecified"))
      (node (ref "U3") (pin "3") (pinfunction "TK4/SDA/MISO/PWM3P/ADC4/P1.4_3") (pintype "input"))
    )
    (net (code "18") (name "MCU_DC1") (class "Default")
      (node (ref "Q5") (pin "1") (pinfunction "G_1") (pintype "unspecified"))
      (node (ref "R15") (pin "2") (pinfunction "2_2") (pintype "unspecified"))
      (node (ref "U3") (pin "32") (pinfunction "SEG11/TK15/T4CLKO_2/PWM8_3/TxD4/ADC11/AD3/P0.3_32") (pintype "input"))
    )
    (net (code "19") (name "MCU_DC2") (class "Default")
      (node (ref "Q6") (pin "1") (pinfunction "G_1") (pintype "unspecified"))
      (node (ref "R16") (pin "2") (pinfunction "2_2") (pintype "unspecified"))
      (node (ref "U3") (pin "31") (pinfunction "SEG10/TK14/T4_2/PWM7_3/RxD4/ADC10/AD2/P0.2_31") (pintype "input"))
    )
    (net (code "20") (name "MCU_DC3") (class "Default")
      (node (ref "Q7") (pin "1") (pinfunction "G_1") (pintype "unspecified"))
      (node (ref "R17") (pin "2") (pinfunction "2_2") (pintype "unspecified"))
      (node (ref "U3") (pin "30") (pinfunction "SEG9/TK13/T3CLKO_2/PWM6_3/TxD3/ADC9/AD1/P0.1_30") (pintype "input"))
    )
    (net (code "21") (name "MCU_DC4") (class "Default")
      (node (ref "Q8") (pin "1") (pinfunction "G_1") (pintype "unspecified"))
      (node (ref "R18") (pin "2") (pinfunction "2_2") (pintype "unspecified"))
      (node (ref "U3") (pin "29") (pinfunction "SEG8/TK12/T3_2/PWM5_3/RxD3/ADC8/AD0/P0.0_29") (pintype "input"))
    )
    (net (code "22") (name "MCU_DC5") (class "Default")
      (node (ref "Q9") (pin "1") (pinfunction "G_1") (pintype "unspecified"))
      (node (ref "R19") (pin "2") (pinfunction "2_2") (pintype "unspecified"))
      (node (ref "U3") (pin "28") (pinfunction "COM7/PWM4N_2/A15/P2.7_28") (pintype "input"))
    )
    (net (code "23") (name "MCU_DC6") (class "Default")
      (node (ref "Q10") (pin "1") (pinfunction "G_1") (pintype "unspecified"))
      (node (ref "R20") (pin "2") (pinfunction "2_2") (pintype "unspecified"))
      (node (ref "U3") (pin "26") (pinfunction "COM5/SCLK_2/SCL_2/PWM3N_2/A13/P2.5_26") (pintype "input"))
    )
    (net (code "24") (name "MCU_DC7") (class "Default")
      (node (ref "Q11") (pin "1") (pinfunction "G_1") (pintype "unspecified"))
      (node (ref "R21") (pin "2") (pinfunction "2_2") (pintype "unspecified"))
      (node (ref "U3") (pin "25") (pinfunction "COM4/MISO_2/SDA_2/PWM3P_2/A12/P2.4_25") (pintype "input"))
    )
    (net (code "25") (name "MCU_DC8") (class "Default")
      (node (ref "Q12") (pin "1") (pinfunction "G_1") (pintype "unspecified"))
      (node (ref "R22") (pin "2") (pinfunction "2_2") (pintype "unspecified"))
      (node (ref "U3") (pin "27") (pinfunction "COM6/PWM4P_2/A14/P2.6_27") (pintype "input"))
    )
    (net (code "26") (name "MCU_FAN_PWM") (class "Default")
      (node (ref "Q14") (pin "1") (pinfunction "G_1") (pintype "unspecified"))
      (node (ref "R31") (pin "2") (pinfunction "2_2") (pintype "unspecified"))
      (node (ref "U3") (pin "7") (pinfunction "TK3/T2CLKO/MOSI/PWM2N/ADC3/P1.3_7") (pintype "input"))
    )
    (net (code "27") (name "MCU_KEY_DOWN") (class "Default")
      (node (ref "R8") (pin "2") (pinfunction "2_2") (pintype "unspecified"))
      (node (ref "SW3") (pin "1") (pinfunction "1_1") (pintype "unspecified"))
      (node (ref "U3") (pin "18") (pinfunction "P3.5/T1/T0CLKO/SS_4/PWMFLT/PWMFLT2/SEG13_18") (pintype "input"))
    )
    (net (code "28") (name "MCU_KEY_SET") (class "Default")
      (node (ref "R9") (pin "2") (pinfunction "2_2") (pintype "unspecified"))
      (node (ref "SW4") (pin "1") (pinfunction "1_1") (pintype "unspecified"))
      (node (ref "U3") (pin "17") (pinfunction "P3.4/T0/T1CLKO/MOSI_4/PWM4P_4/PWM8_2/CMPO/SEG12_17") (pintype "input"))
    )
    (net (code "29") (name "MCU_KEY_UP") (class "Default")
      (node (ref "R7") (pin "2") (pinfunction "2_2") (pintype "unspecified"))
      (node (ref "SW2") (pin "1") (pinfunction "1_1") (pintype "unspecified"))
      (node (ref "U3") (pin "19") (pinfunction "P3.6/T1/T0CLKO/SS_4/PWMFLT/PWMFLT2/SEG13_19") (pintype "input"))
    )
    (net (code "30") (name "MCU_LED") (class "Default")
      (node (ref "LED4") (pin "1") (pinfunction "K_1") (pintype "unspecified"))
      (node (ref "U3") (pin "4") (pinfunction "TK5/SCL/SCLK/PWM3N/ADC5/P1.5_4") (pintype "input"))
    )
    (net (code "31") (name "MCU_RST") (class "Default")
      (node (ref "C8") (pin "1") (pinfunction "1_1") (pintype "input"))
      (node (ref "R5") (pin "1") (pinfunction "1_1") (pintype "unspecified"))
      (node (ref "SW1") (pin "1") (pinfunction "1_1") (pintype "unspecified"))
      (node (ref "U3") (pin "9") (pinfunction "P5.4/NRST/MCLKO/SS/SS_3/PWM2P/PWM6_2/ADC2/T2/TK2/ADC_ETR_9") (pintype "input"))
    )
    (net (code "32") (name "MCU_RXD") (class "Default")
      (node (ref "H2") (pin "2") (pinfunction "2_2") (pintype "unspecified"))
      (node (ref "U3") (pin "13") (pinfunction "P3.0/RxD/INT4_13") (pintype "input"))
    )
    (net (code "33") (name "MCU_SENSOR") (class "Default")
      (node (ref "H3") (pin "2") (pinfunction "2_2") (pintype "unspecified"))
      (node (ref "R6") (pin "1") (pinfunction "1_1") (pintype "unspecified"))
      (node (ref "U3") (pin "15") (pinfunction "P3.2/INT0/SCLK_4/SCL_4/PWMETI/PWMETI2_15") (pintype "input"))
    )
    (net (code "34") (name "MCU_TEST") (class "Default")
      (node (ref "R10") (pin "2") (pinfunction "2_2") (pintype "unspecified"))
      (node (ref "SW5") (pin "1") (pinfunction "1_1") (pintype "unspecified"))
      (node (ref "U3") (pin "6") (pinfunction "Tk7/XTALI/PWM5_2/TxD_3/PWM4N/ADC7/P1.7_6") (pintype "input"))
    )
    (net (code "35") (name "MCU_TXD") (class "Default")
      (node (ref "H2") (pin "3") (pinfunction "3_3") (pintype "unspecified"))
      (node (ref "U3") (pin "14") (pinfunction "P3.1/TxD_14") (pintype "input"))
    )
    (net (code "36") (name "Net-(D1-K)") (class "Default")
      (node (ref "D1") (pin "2") (pinfunction "K_2") (pintype "unspecified"))
      (node (ref "L1") (pin "1") (pinfunction "1_1") (pintype "unspecified"))
      (node (ref "U1") (pin "2") (pinfunction "OUT_2") (pintype "unspecified"))
    )
    (net (code "37") (name "Net-(LED1-C)") (class "Default")
      (node (ref "LED1") (pin "1") (pinfunction "C_1") (pintype "unspecified"))
      (node (ref "R1") (pin "2") (pinfunction "2_2") (pintype "unspecified"))
    )
    (net (code "38") (name "Net-(LED2-K)") (class "Default")
      (node (ref "LED2") (pin "1") (pinfunction "K_1") (pintype "unspecified"))
      (node (ref "R2") (pin "2") (pinfunction "2_2") (pintype "input"))
    )
    (net (code "39") (name "Net-(LED3-A)") (class "Default")
      (node (ref "LED3") (pin "2") (pinfunction "A_2") (pintype "unspecified"))
      (node (ref "R4") (pin "1") (pinfunction "1_1") (pintype "unspecified"))
    )
    (net (code "40") (name "Net-(LED4-A)") (class "Default")
      (node (ref "LED4") (pin "2") (pinfunction "A_2") (pintype "unspecified"))
      (node (ref "R11") (pin "1") (pinfunction "1_1") (pintype "input"))
    )
    (net (code "41") (name "Net-(LED5-A)") (class "Default")
      (node (ref "LED5") (pin "11") (pinfunction "A_11") (pintype "unspecified"))
      (node (ref "R29") (pin "1") (pinfunction "1_1") (pintype "input"))
    )
    (net (code "42") (name "Net-(LED5-B)") (class "Default")
      (node (ref "LED5") (pin "7") (pinfunction "B_7") (pintype "unspecified"))
      (node (ref "R30") (pin "2") (pinfunction "2_2") (pintype "input"))
    )
    (net (code "43") (name "Net-(LED5-C)") (class "Default")
      (node (ref "LED5") (pin "4") (pinfunction "C_4") (pintype "unspecified"))
      (node (ref "R26") (pin "2") (pinfunction "2_2") (pintype "input"))
    )
    (net (code "44") (name "Net-(LED5-D)") (class "Default")
      (node (ref "LED5") (pin "2") (pinfunction "D_2") (pintype "unspecified"))
      (node (ref "R24") (pin "2") (pinfunction "2_2") (pintype "input"))
    )
    (net (code "45") (name "Net-(LED5-DP)") (class "Default")
      (node (ref "LED5") (pin "3") (pinfunction "DP_3") (pintype "unspecified"))
      (node (ref "R25") (pin "2") (pinfunction "2_2") (pintype "input"))
    )
    (net (code "46") (name "Net-(LED5-E)") (class "Default")
      (node (ref "LED5") (pin "1") (pinfunction "E_1") (pintype "unspecified"))
      (node (ref "R23") (pin "2") (pinfunction "2_2") (pintype "input"))
    )
    (net (code "47") (name "Net-(LED5-F)") (class "Default")
      (node (ref "LED5") (pin "10") (pinfunction "F_10") (pintype "unspecified"))
      (node (ref "R28") (pin "1") (pinfunction "1_1") (pintype "input"))
    )
    (net (code "48") (name "Net-(LED5-G)") (class "Default")
      (node (ref "LED5") (pin "5") (pinfunction "G_5") (pintype "unspecified"))
      (node (ref "R27") (pin "2") (pinfunction "2_2") (pintype "input"))
    )
    (net (code "49") (name "Net-(Q1-G)") (class "Default")
      (node (ref "Q1") (pin "1") (pinfunction "G_1") (pintype "unspecified"))
      (node (ref "U2") (pin "5") (pinfunction "VOUT_5") (pintype "unspecified"))
    )
    (net (code "50") (name "Net-(Q1-S)") (class "Default")
      (node (ref "F1") (pin "1") (pinfunction "1_1") (pintype "unspecified"))
      (node (ref "Q1") (pin "3") (pinfunction "S_3") (pintype "unspecified"))
    )
    (net (code "51") (name "Net-(Q14-D)") (class "Default")
      (node (ref "Q14") (pin "3") (pinfunction "D_3") (pintype "unspecified"))
      (node (ref "U2") (pin "3") (pinfunction "CATHODE_3") (pintype "unspecified"))
    )
    (net (code "52") (name "Net-(U2-ANODE)") (class "Default")
      (node (ref "R3") (pin "2") (pinfunction "2_2") (pintype "unspecified"))
      (node (ref "U2") (pin "1") (pinfunction "ANODE_1") (pintype "unspecified"))
    )
    (net (code "53") (name "Net-(U3-TCap)") (class "Default")
      (node (ref "C7") (pin "2") (pinfunction "2_2") (pintype "unspecified"))
      (node (ref "U3") (pin "8") (pinfunction "TCap_8") (pintype "input"))
    )
    (net (code "54") (name "VSUPPLY") (class "Default")
      (node (ref "C1") (pin "1") (pinfunction "1_1") (pintype "input"))
      (node (ref "C3") (pin "2") (pinfunction "2_2") (pintype "unspecified"))
      (node (ref "C4") (pin "2") (pinfunction "2_2") (pintype "unspecified"))
      (node (ref "DC1") (pin "1") (pinfunction "1_1") (pintype "unspecified"))
      (node (ref "F1") (pin "2") (pinfunction "2_2") (pintype "unspecified"))
      (node (ref "LED1") (pin "2") (pinfunction "A_2") (pintype "unspecified"))
      (node (ref "U1") (pin "1") (pinfunction "VIN_1") (pintype "unspecified"))
      (node (ref "U2") (pin "6") (pinfunction "VCC_6") (pintype "unspecified"))
    )
    (net (code "55") (name "unconnected-(DC1-Pad3)") (class "Default")
      (node (ref "DC1") (pin "3") (pinfunction "3_3") (pintype "unspecified+no_connect"))
    )
    (net (code "56") (name "unconnected-(LED5-NC-Pad6)") (class "Default")
      (node (ref "LED5") (pin "6") (pinfunction "NC_6") (pintype "unspecified+no_connect"))
    )
    (net (code "57") (name "unconnected-(U2-NC-Pad2)") (class "Default")
      (node (ref "U2") (pin "2") (pinfunction "NC_2") (pintype "unspecified+no_connect"))
    )
    (net (code "58") (name "unconnected-(U3-P2.0{slash}A8{slash}PWM1P_2{slash}PWM5{slash}COM0-Pad21)") (class "Default")
      (node (ref "U3") (pin "21") (pinfunction "P2.0/A8/PWM1P_2/PWM5/COM0_21") (pintype "input+no_connect"))
    )
    (net (code "59") (name "unconnected-(U3-P2.1{slash}A9{slash}PWM1N_2{slash}PWM6{slash}COM1-Pad22)") (class "Default")
      (node (ref "U3") (pin "22") (pinfunction "P2.1/A9/PWM1N_2/PWM6/COM1_22") (pintype "input+no_connect"))
    )
    (net (code "60") (name "unconnected-(U3-P2.2{slash}A10{slash}PWM2P_2{slash}PWM7{slash}SS_2{slash}COM2-Pad23)") (class "Default")
      (node (ref "U3") (pin "23") (pinfunction "P2.2/A10/PWM2P_2/PWM7/SS_2/COM2_23") (pintype "input+no_connect"))
    )
    (net (code "61") (name "unconnected-(U3-P2.3{slash}A11{slash}PWM2N_2{slash}PWM8{slash}MOSI_2{slash}COM3-Pad24)") (class "Default")
      (node (ref "U3") (pin "24") (pinfunction "P2.3/A11/PWM2N_2/PWM8/MOSI_2/COM3_24") (pintype "input+no_connect"))
    )
    (net (code "62") (name "unconnected-(U3-P3.3{slash}INT1{slash}MISO_4{slash}SDA_4{slash}PWM4N_4{slash}PWM7_2-Pad16)") (class "Default")
      (node (ref "U3") (pin "16") (pinfunction "P3.3/INT1/MISO_4/SDA_4/PWM4N_4/PWM7_2_16") (pintype "input+no_connect"))
    )
    (net (code "63") (name "unconnected-(U3-P3.7{slash}INT3{slash}TxD_2{slash}CMP+{slash}SEG15-Pad20)") (class "Default")
      (node (ref "U3") (pin "20") (pinfunction "P3.7/INT3/TxD_2/CMP+/SEG15_20") (pintype "input+no_connect"))
    )
    (net (code "64") (name "unconnected-(U3-TK6{slash}XTALO{slash}MCLKO_2{slash}RxD_3{slash}PWM4P{slash}ADC6{slash}P1.6-Pad5)") (class "Default")
      (node (ref "U3") (pin "5") (pinfunction "TK6/XTALO/MCLKO_2/RxD_3/PWM4P/ADC6/P1.6_5") (pintype "input+no_connect"))
    )
  )
)
